# STM32.net
KiCad netlist of a schematic drawn in Altium Designer
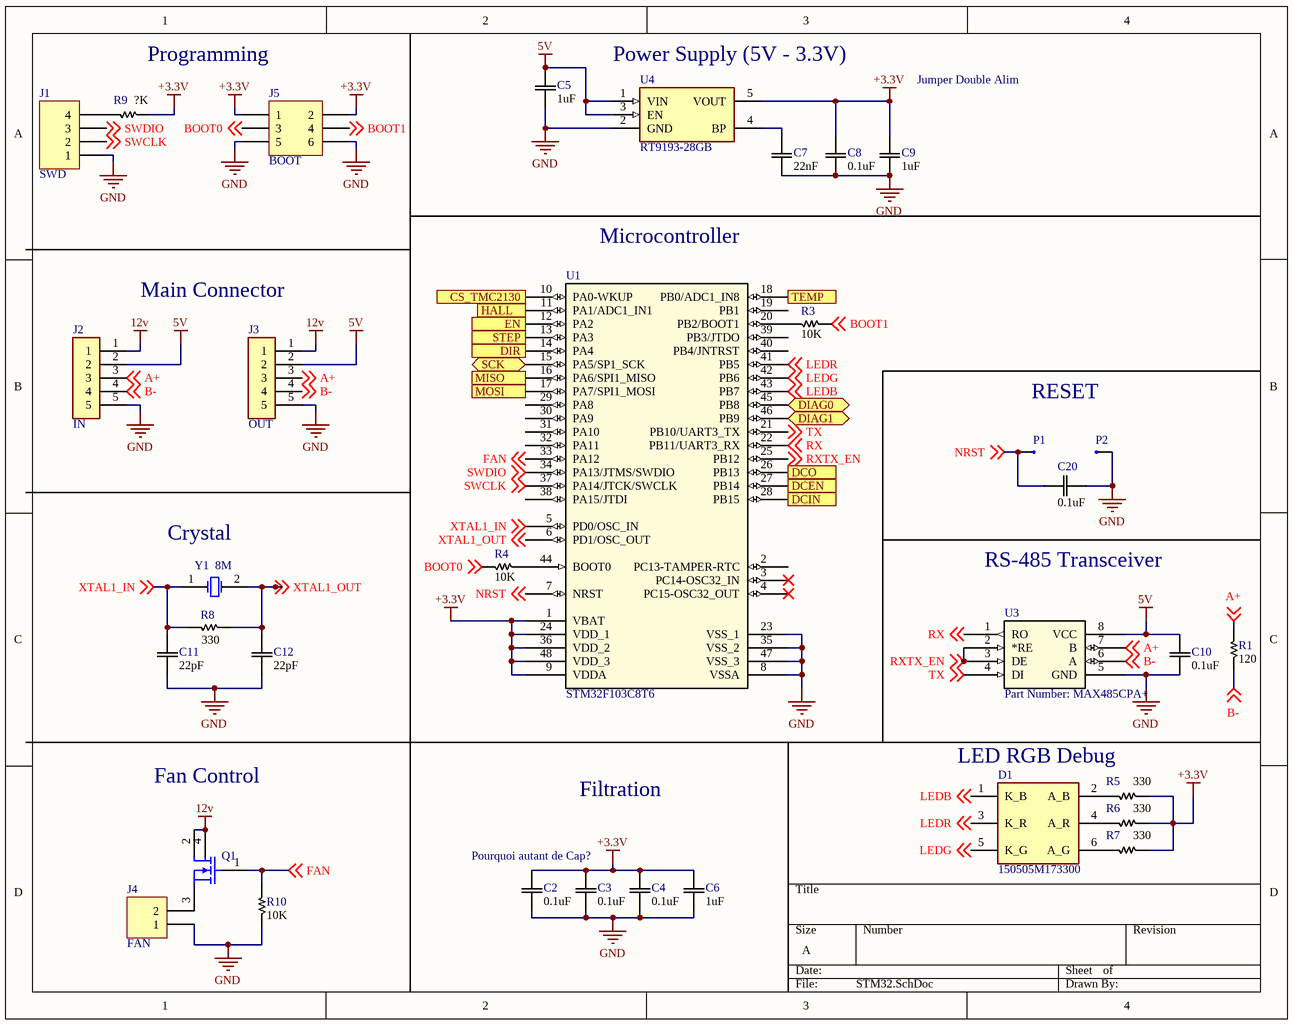
[diagram p0: STM32.SchDoc]

(export (version "E")
  (design (tool "Eeschema 10.0.6"))
  (components
    (comp (ref "C2")
      (value "0.1uF")
      (footprint "0603")
      (description "Capacitor SMD 1206")
      (fields
        (field (name "MANUFACTURER_PART_NUMBER") "12065A820JAT2A")
        (field (name "Comment") "Capacitor 1206")
        (field (name "COPYRIGHT") "Copyright (C) 2018 Accelerated Designs. All rights reserved")
      )
      (libsource (lib "Schematic_Emile") (part "Capacitor 1206"))
    )
    (comp (ref "C3")
      (value "0.1uF")
      (footprint "0603")
      (description "Capacitor SMD 1206")
      (fields
        (field (name "MANUFACTURER_PART_NUMBER") "12065A820JAT2A")
        (field (name "Comment") "Capacitor 1206")
        (field (name "COPYRIGHT") "Copyright (C) 2018 Accelerated Designs. All rights reserved")
      )
      (libsource (lib "Schematic_Emile") (part "Capacitor 1206"))
    )
    (comp (ref "C4")
      (value "0.1uF")
      (footprint "0603")
      (description "Capacitor SMD 1206")
      (fields
        (field (name "MANUFACTURER_PART_NUMBER") "12065A820JAT2A")
        (field (name "Comment") "Capacitor 1206")
        (field (name "COPYRIGHT") "Copyright (C) 2018 Accelerated Designs. All rights reserved")
      )
      (libsource (lib "Schematic_Emile") (part "Capacitor 1206"))
    )
    (comp (ref "C5")
      (value "1uF")
      (footprint "0603")
      (description "Capacitor SMD 1206")
      (fields
        (field (name "MANUFACTURER_PART_NUMBER") "12065A820JAT2A")
        (field (name "Comment") "Capacitor 1206")
        (field (name "COPYRIGHT") "Copyright (C) 2018 Accelerated Designs. All rights reserved")
      )
      (libsource (lib "Schematic_Emile") (part "Capacitor 1206"))
    )
    (comp (ref "C6")
      (value "1uF")
      (footprint "0603")
      (description "Capacitor SMD 1206")
      (fields
        (field (name "MANUFACTURER_PART_NUMBER") "12065A820JAT2A")
        (field (name "Comment") "Capacitor 1206")
        (field (name "COPYRIGHT") "Copyright (C) 2018 Accelerated Designs. All rights reserved")
      )
      (libsource (lib "Schematic_Emile") (part "Capacitor 1206"))
    )
    (comp (ref "C7")
      (value "22nF")
      (footprint "0603")
      (description "Capacitor SMD 1206")
      (fields
        (field (name "MANUFACTURER_PART_NUMBER") "12065A820JAT2A")
        (field (name "Comment") "Capacitor 1206")
        (field (name "COPYRIGHT") "Copyright (C) 2018 Accelerated Designs. All rights reserved")
      )
      (libsource (lib "Schematic_Emile") (part "Capacitor 1206"))
    )
    (comp (ref "C8")
      (value "0.1uF")
      (footprint "0603")
      (description "Capacitor SMD 1206")
      (fields
        (field (name "MANUFACTURER_PART_NUMBER") "12065A820JAT2A")
        (field (name "Comment") "Capacitor 1206")
        (field (name "COPYRIGHT") "Copyright (C) 2018 Accelerated Designs. All rights reserved")
      )
      (libsource (lib "Schematic_Emile") (part "Capacitor 1206"))
    )
    (comp (ref "C9")
      (value "1uF")
      (footprint "0603")
      (description "Capacitor SMD 1206")
      (fields
        (field (name "MANUFACTURER_PART_NUMBER") "12065A820JAT2A")
        (field (name "Comment") "Capacitor 1206")
        (field (name "COPYRIGHT") "Copyright (C) 2018 Accelerated Designs. All rights reserved")
      )
      (libsource (lib "Schematic_Emile") (part "Capacitor 1206"))
    )
    (comp (ref "C10")
      (value "0.1uF")
      (footprint "0603")
      (description "Capacitor SMD 1206")
      (fields
        (field (name "MANUFACTURER_PART_NUMBER") "12065A820JAT2A")
        (field (name "Comment") "Capacitor 1206")
        (field (name "COPYRIGHT") "Copyright (C) 2018 Accelerated Designs. All rights reserved")
      )
      (libsource (lib "Schematic_Emile") (part "Capacitor 1206"))
    )
    (comp (ref "C11")
      (value "22pF")
      (footprint "0603")
      (description "Capacitor SMD 1206")
      (fields
        (field (name "MANUFACTURER_PART_NUMBER") "12065A820JAT2A")
        (field (name "Comment") "Capacitor 1206")
        (field (name "COPYRIGHT") "Copyright (C) 2018 Accelerated Designs. All rights reserved")
      )
      (libsource (lib "Schematic_Emile") (part "Capacitor 1206"))
    )
    (comp (ref "C12")
      (value "22pF")
      (footprint "0603")
      (description "Capacitor SMD 1206")
      (fields
        (field (name "MANUFACTURER_PART_NUMBER") "12065A820JAT2A")
        (field (name "Comment") "Capacitor 1206")
        (field (name "COPYRIGHT") "Copyright (C) 2018 Accelerated Designs. All rights reserved")
      )
      (libsource (lib "Schematic_Emile") (part "Capacitor 1206"))
    )
    (comp (ref "C20")
      (value "0.1uF")
      (footprint "0603")
      (description "Capacitor SMD 1206")
      (fields
        (field (name "MANUFACTURER_PART_NUMBER") "12065A820JAT2A")
        (field (name "Comment") "Capacitor 1206")
        (field (name "COPYRIGHT") "Copyright (C) 2018 Accelerated Designs. All rights reserved")
      )
      (libsource (lib "Schematic_Emile") (part "Capacitor 1206"))
    )
    (comp (ref "D1")
      (value "150505M173300")
      (footprint "LED 5050")
      (description "LED")
      (fields
        (field (name "MOUSER PART NUMBER") "710-150505M173300")
        (field (name "RS PART NUMBER") "1766248P")
      )
      (libsource (lib "Schematic_Emile") (part "150505M173300"))
    )
    (comp (ref "J1")
      (value "SWD")
      (footprint "HDR1X4")
      (description "Header, 4-Pin")
      (fields (field (name "PUBLISHER") "Altium Limited"))
      (libsource (lib "Miscellaneous Connectors") (part "Header 4"))
    )
    (comp (ref "J2")
      (value "IN")
      (footprint "JST 5POS 2.5mm 90°")
      (description "Connector")
      (fields (field (name "MANUFACTURER_PART_NUMBER") "S5B-XH-A-1(LF)(SN)"))
      (libsource (lib "Schematic_Emile") (part "JST 5POS"))
    )
    (comp (ref "J3")
      (value "OUT")
      (footprint "JST 5POS 2.5mm 90°")
      (description "Connector")
      (fields (field (name "MANUFACTURER_PART_NUMBER") "S5B-XH-A-1(LF)(SN)"))
      (libsource (lib "Schematic_Emile") (part "JST 5POS"))
    )
    (comp (ref "J4")
      (value "FAN")
      (footprint "HDR1X2")
      (description "Header, 2-Pin")
      (fields (field (name "PUBLISHER") "Altium Limited"))
      (libsource (lib "Miscellaneous Connectors") (part "Header 2"))
    )
    (comp (ref "J5")
      (value "BOOT")
      (footprint "HDR2X3")
      (description "Header, 3-Pin, Dual row")
      (fields (field (name "PUBLISHER") "Altium Limited"))
      (libsource (lib "Miscellaneous Connectors") (part "Header 3X2"))
    )
    (comp (ref "P1")
      (value "Pad")
      (footprint "PAD")
      (description "SMD Pad for contact")
      (libsource (lib "Schematic_Emile") (part "Pad"))
    )
    (comp (ref "P2")
      (value "Pad")
      (footprint "PAD")
      (description "SMD Pad for contact")
      (libsource (lib "Schematic_Emile") (part "Pad"))
    )
    (comp (ref "Q1")
      (value "MOSFET N-CH")
      (footprint "SOT223_M")
      (description "55V 7A SOT223")
      (libsource (lib "Schematic_Emile") (part "MOSFET N-CH"))
    )
    (comp (ref "R1")
      (value "120")
      (footprint "0603")
      (description "Resistor 1206 SMD")
      (fields
        (field (name "MANUFACTURER_PART_NUMBER") "ERJ8CWFR024V")
        (field (name "Comment") "Resistor 1206")
        (field (name "COPYRIGHT") "Copyright (C) 2018 Accelerated Designs. All rights reserved")
      )
      (libsource (lib "Schematic_Emile") (part "Resistor 1206"))
    )
    (comp (ref "R3")
      (value "10K")
      (footprint "0603")
      (description "Resistor 1206 SMD")
      (fields
        (field (name "MANUFACTURER_PART_NUMBER") "ERJ8CWFR024V")
        (field (name "Comment") "Resistor 1206")
        (field (name "COPYRIGHT") "Copyright (C) 2018 Accelerated Designs. All rights reserved")
      )
      (libsource (lib "Schematic_Emile") (part "Resistor 1206"))
    )
    (comp (ref "R4")
      (value "10K")
      (footprint "0603")
      (description "Resistor 1206 SMD")
      (fields
        (field (name "MANUFACTURER_PART_NUMBER") "ERJ8CWFR024V")
        (field (name "Comment") "Resistor 1206")
        (field (name "COPYRIGHT") "Copyright (C) 2018 Accelerated Designs. All rights reserved")
      )
      (libsource (lib "Schematic_Emile") (part "Resistor 1206"))
    )
    (comp (ref "R5")
      (value "330")
      (footprint "0603")
      (description "Resistor 1206 SMD")
      (fields
        (field (name "MANUFACTURER_PART_NUMBER") "ERJ8CWFR024V")
        (field (name "Comment") "Resistor 1206")
        (field (name "COPYRIGHT") "Copyright (C) 2018 Accelerated Designs. All rights reserved")
      )
      (libsource (lib "Schematic_Emile") (part "Resistor 1206"))
    )
    (comp (ref "R6")
      (value "330")
      (footprint "0603")
      (description "Resistor 1206 SMD")
      (fields
        (field (name "MANUFACTURER_PART_NUMBER") "ERJ8CWFR024V")
        (field (name "Comment") "Resistor 1206")
        (field (name "COPYRIGHT") "Copyright (C) 2018 Accelerated Designs. All rights reserved")
      )
      (libsource (lib "Schematic_Emile") (part "Resistor 1206"))
    )
    (comp (ref "R7")
      (value "330")
      (footprint "0603")
      (description "Resistor 1206 SMD")
      (fields
        (field (name "MANUFACTURER_PART_NUMBER") "ERJ8CWFR024V")
        (field (name "Comment") "Resistor 1206")
        (field (name "COPYRIGHT") "Copyright (C) 2018 Accelerated Designs. All rights reserved")
      )
      (libsource (lib "Schematic_Emile") (part "Resistor 1206"))
    )
    (comp (ref "R8")
      (value "330")
      (footprint "0603")
      (description "Resistor 1206 SMD")
      (fields
        (field (name "MANUFACTURER_PART_NUMBER") "ERJ8CWFR024V")
        (field (name "Comment") "Resistor 1206")
        (field (name "COPYRIGHT") "Copyright (C) 2018 Accelerated Designs. All rights reserved")
      )
      (libsource (lib "Schematic_Emile") (part "Resistor 1206"))
    )
    (comp (ref "R9")
      (value "?K")
      (footprint "0603")
      (description "Resistor 1206 SMD")
      (fields
        (field (name "MANUFACTURER_PART_NUMBER") "ERJ8CWFR024V")
        (field (name "Comment") "Resistor 1206")
        (field (name "COPYRIGHT") "Copyright (C) 2018 Accelerated Designs. All rights reserved")
      )
      (libsource (lib "Schematic_Emile") (part "Resistor 1206"))
    )
    (comp (ref "R10")
      (value "10K")
      (footprint "0603")
      (description "Resistor 1206 SMD")
      (fields
        (field (name "MANUFACTURER_PART_NUMBER") "ERJ8CWFR024V")
        (field (name "Comment") "Resistor 1206")
        (field (name "COPYRIGHT") "Copyright (C) 2018 Accelerated Designs. All rights reserved")
      )
      (libsource (lib "Schematic_Emile") (part "Resistor 1206"))
    )
    (comp (ref "U1")
      (value "STM32F103C8T6")
      (footprint "LQFP-48")
      (description "Integrated Circuit STM32")
      (fields (field (name "COPYRIGHT") "Copyright (C) 2018 Accelerated Designs. All rights reserved"))
      (libsource (lib "Schematic_Emile") (part "STM32F103C8T6"))
    )
    (comp (ref "U3")
      (value "Part Number: MAX485CPA+")
      (footprint "DIP 8 - 3D")
      (description "RS485 Communication")
      (fields
        (field (name "MANUFACTURER_PART_NUMBER") "MAX485CPA+")
        (field (name "COPYRIGHT") "Copyright (C) 2018 Accelerated Designs. All rights reserved")
      )
      (libsource (lib "Schematic_Emile") (part "MAX485CPA+"))
    )
    (comp (ref "U4")
      (value "RT9193-28GB")
      (footprint "SamacSys:SOT94P279X130-5N")
      (description "Voltage Regulator 3.3V")
      (libsource (lib "Schematic_Emile") (part "RT9193-28GB"))
    )
    (comp (ref "Y1")
      (value "8M")
      (footprint "ATS080B-E")
      (description "Crystal Oscillator")
      (fields (field (name "PUBLISHER") "Altium Limited"))
      (libsource (lib "Miscellaneous Devices") (part "XTAL"))
    )
  )
  (nets
    (net (code "1") (name "+3.3V") (class "Default")
      (node (ref "C2") (pin "2") (pinfunction "2_2") (pintype "passive"))
      (node (ref "C3") (pin "2") (pinfunction "2_2") (pintype "passive"))
      (node (ref "C4") (pin "2") (pinfunction "2_2") (pintype "passive"))
      (node (ref "C6") (pin "2") (pinfunction "2_2") (pintype "passive"))
      (node (ref "C8") (pin "2") (pinfunction "2_2") (pintype "passive"))
      (node (ref "C9") (pin "2") (pinfunction "2_2") (pintype "passive"))
      (node (ref "J5") (pin "1") (pinfunction "1_1") (pintype "passive"))
      (node (ref "J5") (pin "2") (pinfunction "2_2") (pintype "passive"))
      (node (ref "R5") (pin "2") (pinfunction "2_2") (pintype "passive"))
      (node (ref "R6") (pin "2") (pinfunction "2_2") (pintype "passive"))
      (node (ref "R7") (pin "2") (pinfunction "2_2") (pintype "passive"))
      (node (ref "R9") (pin "2") (pinfunction "2_2") (pintype "passive"))
      (node (ref "U1") (pin "1") (pinfunction "VBAT_1") (pintype "power_in"))
      (node (ref "U1") (pin "24") (pinfunction "VDD_1_24") (pintype "power_in"))
      (node (ref "U1") (pin "36") (pinfunction "VDD_2_36") (pintype "power_in"))
      (node (ref "U1") (pin "48") (pinfunction "VDD_3_48") (pintype "power_in"))
      (node (ref "U1") (pin "9") (pinfunction "VDDA_9") (pintype "power_in"))
      (node (ref "U4") (pin "5") (pinfunction "VOUT_5") (pintype "passive"))
    )
    (net (code "2") (name "/CS_TMC2130") (class "Default")
      (node (ref "U1") (pin "10") (pinfunction "PA0-WKUP_10") (pintype "bidirectional"))
    )
    (net (code "3") (name "/DCEN") (class "Default")
      (node (ref "U1") (pin "27") (pinfunction "PB14_27") (pintype "bidirectional"))
    )
    (net (code "4") (name "/DCIN") (class "Default")
      (node (ref "U1") (pin "28") (pinfunction "PB15_28") (pintype "bidirectional"))
    )
    (net (code "5") (name "/DCO") (class "Default")
      (node (ref "U1") (pin "26") (pinfunction "PB13_26") (pintype "bidirectional"))
    )
    (net (code "6") (name "/DIAG0") (class "Default")
      (node (ref "U1") (pin "45") (pinfunction "PB8_45") (pintype "bidirectional"))
    )
    (net (code "7") (name "/DIAG1") (class "Default")
      (node (ref "U1") (pin "46") (pinfunction "PB9_46") (pintype "bidirectional"))
    )
    (net (code "8") (name "/DIR") (class "Default")
      (node (ref "U1") (pin "14") (pinfunction "PA4_14") (pintype "bidirectional"))
    )
    (net (code "9") (name "/EN") (class "Default")
      (node (ref "U1") (pin "12") (pinfunction "PA2_12") (pintype "bidirectional"))
    )
    (net (code "10") (name "/HALL") (class "Default")
      (node (ref "U1") (pin "11") (pinfunction "PA1/ADC1_IN1_11") (pintype "bidirectional"))
    )
    (net (code "11") (name "/MISO") (class "Default")
      (node (ref "U1") (pin "16") (pinfunction "PA6/SPI1_MISO_16") (pintype "bidirectional"))
    )
    (net (code "12") (name "/MOSI") (class "Default")
      (node (ref "U1") (pin "17") (pinfunction "PA7/SPI1_MOSI_17") (pintype "bidirectional"))
    )
    (net (code "13") (name "/SCK") (class "Default")
      (node (ref "U1") (pin "15") (pinfunction "PA5/SP1_SCK_15") (pintype "bidirectional"))
    )
    (net (code "14") (name "/STEP") (class "Default")
      (node (ref "U1") (pin "13") (pinfunction "PA3_13") (pintype "bidirectional"))
    )
    (net (code "15") (name "/TEMP") (class "Default")
      (node (ref "U1") (pin "18") (pinfunction "PB0/ADC1_IN8_18") (pintype "bidirectional"))
    )
    (net (code "16") (name "5V") (class "Default")
      (node (ref "C10") (pin "2") (pinfunction "2_2") (pintype "passive"))
      (node (ref "C5") (pin "2") (pinfunction "2_2") (pintype "passive"))
      (node (ref "J2") (pin "2") (pinfunction "2_2") (pintype "passive"))
      (node (ref "J3") (pin "2") (pinfunction "2_2") (pintype "passive"))
      (node (ref "U3") (pin "8") (pinfunction "VCC_8") (pintype "power_in"))
      (node (ref "U4") (pin "1") (pinfunction "VIN_1") (pintype "input"))
      (node (ref "U4") (pin "3") (pinfunction "EN_3") (pintype "input"))
    )
    (net (code "17") (name "12v") (class "Default")
      (node (ref "J2") (pin "1") (pinfunction "1_1") (pintype "passive"))
      (node (ref "J3") (pin "1") (pinfunction "1_1") (pintype "passive"))
      (node (ref "Q1") (pin "2") (pinfunction "D_2") (pintype "passive"))
      (node (ref "Q1") (pin "4") (pinfunction "D_4") (pintype "passive"))
    )
    (net (code "18") (name "A+") (class "Default")
      (node (ref "J2") (pin "3") (pinfunction "3_3") (pintype "passive"))
      (node (ref "J3") (pin "3") (pinfunction "3_3") (pintype "passive"))
      (node (ref "R1") (pin "2") (pinfunction "2_2") (pintype "passive"))
      (node (ref "U3") (pin "7") (pinfunction "B_7") (pintype "bidirectional"))
    )
    (net (code "19") (name "B-") (class "Default")
      (node (ref "J2") (pin "4") (pinfunction "4_4") (pintype "passive"))
      (node (ref "J3") (pin "4") (pinfunction "4_4") (pintype "passive"))
      (node (ref "R1") (pin "1") (pinfunction "1_1") (pintype "passive"))
      (node (ref "U3") (pin "6") (pinfunction "A_6") (pintype "bidirectional"))
    )
    (net (code "20") (name "BOOT0") (class "Default")
      (node (ref "J5") (pin "3") (pinfunction "3_3") (pintype "passive"))
      (node (ref "R4") (pin "1") (pinfunction "1_1") (pintype "passive"))
    )
    (net (code "21") (name "BOOT1") (class "Default")
      (node (ref "J5") (pin "4") (pinfunction "4_4") (pintype "passive"))
      (node (ref "R3") (pin "2") (pinfunction "2_2") (pintype "passive"))
    )
    (net (code "22") (name "FAN") (class "Default")
      (node (ref "Q1") (pin "1") (pinfunction "G_1") (pintype "passive"))
      (node (ref "R10") (pin "2") (pinfunction "2_2") (pintype "passive"))
      (node (ref "U1") (pin "33") (pinfunction "PA12_33") (pintype "bidirectional"))
    )
    (net (code "23") (name "GND") (class "Default")
      (node (ref "C10") (pin "1") (pinfunction "1_1") (pintype "passive"))
      (node (ref "C11") (pin "1") (pinfunction "1_1") (pintype "passive"))
      (node (ref "C12") (pin "1") (pinfunction "1_1") (pintype "passive"))
      (node (ref "C2") (pin "1") (pinfunction "1_1") (pintype "passive"))
      (node (ref "C20") (pin "1") (pinfunction "1_1") (pintype "passive"))
      (node (ref "C3") (pin "1") (pinfunction "1_1") (pintype "passive"))
      (node (ref "C4") (pin "1") (pinfunction "1_1") (pintype "passive"))
      (node (ref "C5") (pin "1") (pinfunction "1_1") (pintype "passive"))
      (node (ref "C6") (pin "1") (pinfunction "1_1") (pintype "passive"))
      (node (ref "C7") (pin "1") (pinfunction "1_1") (pintype "passive"))
      (node (ref "C8") (pin "1") (pinfunction "1_1") (pintype "passive"))
      (node (ref "C9") (pin "1") (pinfunction "1_1") (pintype "passive"))
      (node (ref "J1") (pin "1") (pinfunction "1_1") (pintype "passive"))
      (node (ref "J2") (pin "5") (pinfunction "5_5") (pintype "passive"))
      (node (ref "J3") (pin "5") (pinfunction "5_5") (pintype "passive"))
      (node (ref "J4") (pin "1") (pinfunction "1_1") (pintype "passive"))
      (node (ref "J5") (pin "5") (pinfunction "5_5") (pintype "passive"))
      (node (ref "J5") (pin "6") (pinfunction "6_6") (pintype "passive"))
      (node (ref "P2") (pin "0") (pinfunction "0_0") (pintype "passive"))
      (node (ref "R10") (pin "1") (pinfunction "1_1") (pintype "passive"))
      (node (ref "U1") (pin "23") (pinfunction "VSS_1_23") (pintype "power_in"))
      (node (ref "U1") (pin "35") (pinfunction "VSS_2_35") (pintype "power_in"))
      (node (ref "U1") (pin "47") (pinfunction "VSS_3_47") (pintype "power_in"))
      (node (ref "U1") (pin "8") (pinfunction "VSSA_8") (pintype "power_in"))
      (node (ref "U3") (pin "5") (pinfunction "GND_5") (pintype "power_in"))
      (node (ref "U4") (pin "2") (pinfunction "GND_2") (pintype "power_in"))
    )
    (net (code "24") (name "LEDB") (class "Default")
      (node (ref "D1") (pin "1") (pinfunction "K_B_1") (pintype "passive"))
      (node (ref "U1") (pin "43") (pinfunction "PB7_43") (pintype "bidirectional"))
    )
    (net (code "25") (name "LEDG") (class "Default")
      (node (ref "D1") (pin "5") (pinfunction "K_G_5") (pintype "passive"))
      (node (ref "U1") (pin "42") (pinfunction "PB6_42") (pintype "bidirectional"))
    )
    (net (code "26") (name "LEDR") (class "Default")
      (node (ref "D1") (pin "3") (pinfunction "K_R_3") (pintype "passive"))
      (node (ref "U1") (pin "41") (pinfunction "PB5_41") (pintype "bidirectional"))
    )
    (net (code "27") (name "NRST") (class "Default")
      (node (ref "C20") (pin "2") (pinfunction "2_2") (pintype "passive"))
      (node (ref "P1") (pin "0") (pinfunction "0_0") (pintype "passive"))
      (node (ref "U1") (pin "7") (pinfunction "NRST_7") (pintype "bidirectional"))
    )
    (net (code "28") (name "Net-(D1-A_B)") (class "Default")
      (node (ref "D1") (pin "2") (pinfunction "A_B_2") (pintype "passive"))
      (node (ref "R5") (pin "1") (pinfunction "1_1") (pintype "passive"))
    )
    (net (code "29") (name "Net-(D1-A_G)") (class "Default")
      (node (ref "D1") (pin "6") (pinfunction "A_G_6") (pintype "passive"))
      (node (ref "R7") (pin "1") (pinfunction "1_1") (pintype "passive"))
    )
    (net (code "30") (name "Net-(D1-A_R)") (class "Default")
      (node (ref "D1") (pin "4") (pinfunction "A_R_4") (pintype "passive"))
      (node (ref "R6") (pin "1") (pinfunction "1_1") (pintype "passive"))
    )
    (net (code "31") (name "Net-(J1-Pad4)") (class "Default")
      (node (ref "J1") (pin "4") (pinfunction "4_4") (pintype "passive"))
      (node (ref "R9") (pin "1") (pinfunction "1_1") (pintype "passive"))
    )
    (net (code "32") (name "Net-(Q1-S)") (class "Default")
      (node (ref "J4") (pin "2") (pinfunction "2_2") (pintype "passive"))
      (node (ref "Q1") (pin "3") (pinfunction "S_3") (pintype "passive"))
    )
    (net (code "33") (name "Net-(U1-BOOT0)") (class "Default")
      (node (ref "R4") (pin "2") (pinfunction "2_2") (pintype "passive"))
      (node (ref "U1") (pin "44") (pinfunction "BOOT0_44") (pintype "input"))
    )
    (net (code "34") (name "Net-(U1-PB2{slash}BOOT1)") (class "Default")
      (node (ref "R3") (pin "1") (pinfunction "1_1") (pintype "passive"))
      (node (ref "U1") (pin "20") (pinfunction "PB2/BOOT1_20") (pintype "bidirectional"))
    )
    (net (code "35") (name "Net-(U4-BP)") (class "Default")
      (node (ref "C7") (pin "2") (pinfunction "2_2") (pintype "passive"))
      (node (ref "U4") (pin "4") (pinfunction "BP_4") (pintype "passive"))
    )
    (net (code "36") (name "RX") (class "Default")
      (node (ref "U1") (pin "22") (pinfunction "PB11/UART3_RX_22") (pintype "bidirectional"))
      (node (ref "U3") (pin "1") (pinfunction "RO_1") (pintype "output"))
    )
    (net (code "37") (name "RXTX_EN") (class "Default")
      (node (ref "U1") (pin "25") (pinfunction "PB12_25") (pintype "bidirectional"))
      (node (ref "U3") (pin "2") (pinfunction "*RE_2") (pintype "input"))
      (node (ref "U3") (pin "3") (pinfunction "DE_3") (pintype "input"))
    )
    (net (code "38") (name "SWCLK") (class "Default")
      (node (ref "J1") (pin "2") (pinfunction "2_2") (pintype "passive"))
      (node (ref "U1") (pin "37") (pinfunction "PA14/JTCK/SWCLK_37") (pintype "bidirectional"))
    )
    (net (code "39") (name "SWDIO") (class "Default")
      (node (ref "J1") (pin "3") (pinfunction "3_3") (pintype "passive"))
      (node (ref "U1") (pin "34") (pinfunction "PA13/JTMS/SWDIO_34") (pintype "bidirectional"))
    )
    (net (code "40") (name "TX") (class "Default")
      (node (ref "U1") (pin "21") (pinfunction "PB10/UART3_TX_21") (pintype "bidirectional"))
      (node (ref "U3") (pin "4") (pinfunction "DI_4") (pintype "input"))
    )
    (net (code "41") (name "XTAL1_IN") (class "Default")
      (node (ref "C11") (pin "2") (pinfunction "2_2") (pintype "passive"))
      (node (ref "R8") (pin "1") (pinfunction "1_1") (pintype "passive"))
      (node (ref "U1") (pin "5") (pinfunction "PD0/OSC_IN_5") (pintype "bidirectional"))
      (node (ref "Y1") (pin "1") (pinfunction "OSC1_1") (pintype "passive"))
    )
    (net (code "42") (name "XTAL1_OUT") (class "Default")
      (node (ref "C12") (pin "2") (pinfunction "2_2") (pintype "passive"))
      (node (ref "R8") (pin "2") (pinfunction "2_2") (pintype "passive"))
      (node (ref "U1") (pin "6") (pinfunction "PD1/OSC_OUT_6") (pintype "bidirectional"))
      (node (ref "Y1") (pin "2") (pinfunction "OSC2_2") (pintype "passive"))
    )
    (net (code "43") (name "unconnected-(U1-PA8-Pad29)") (class "Default")
      (node (ref "U1") (pin "29") (pinfunction "PA8_29") (pintype "bidirectional"))
    )
    (net (code "44") (name "unconnected-(U1-PA9-Pad30)") (class "Default")
      (node (ref "U1") (pin "30") (pinfunction "PA9_30") (pintype "bidirectional"))
    )
    (net (code "45") (name "unconnected-(U1-PA10-Pad31)") (class "Default")
      (node (ref "U1") (pin "31") (pinfunction "PA10_31") (pintype "bidirectional"))
    )
    (net (code "46") (name "unconnected-(U1-PA11-Pad32)") (class "Default")
      (node (ref "U1") (pin "32") (pinfunction "PA11_32") (pintype "bidirectional"))
    )
    (net (code "47") (name "unconnected-(U1-PA15{slash}JTDI-Pad38)") (class "Default")
      (node (ref "U1") (pin "38") (pinfunction "PA15/JTDI_38") (pintype "bidirectional"))
    )
    (net (code "48") (name "unconnected-(U1-PB1-Pad19)") (class "Default")
      (node (ref "U1") (pin "19") (pinfunction "PB1_19") (pintype "bidirectional"))
    )
    (net (code "49") (name "unconnected-(U1-PB3{slash}JTDO-Pad39)") (class "Default")
      (node (ref "U1") (pin "39") (pinfunction "PB3/JTDO_39") (pintype "bidirectional"))
    )
    (net (code "50") (name "unconnected-(U1-PB4{slash}JNTRST-Pad40)") (class "Default")
      (node (ref "U1") (pin "40") (pinfunction "PB4/JNTRST_40") (pintype "bidirectional"))
    )
    (net (code "51") (name "unconnected-(U1-PC13-TAMPER-RTC-Pad2)") (class "Default")
      (node (ref "U1") (pin "2") (pinfunction "PC13-TAMPER-RTC_2") (pintype "bidirectional"))
    )
    (net (code "52") (name "unconnected-(U1-PC14-OSC32_IN-Pad3)") (class "Default")
      (node (ref "U1") (pin "3") (pinfunction "PC14-OSC32_IN_3") (pintype "bidirectional+no_connect"))
    )
    (net (code "53") (name "unconnected-(U1-PC15-OSC32_OUT-Pad4)") (class "Default")
      (node (ref "U1") (pin "4") (pinfunction "PC15-OSC32_OUT_4") (pintype "bidirectional+no_connect"))
    )
  )
)
